# Sheet1_Young.net
KiCad netlist of a schematic drawn in Altium Designer
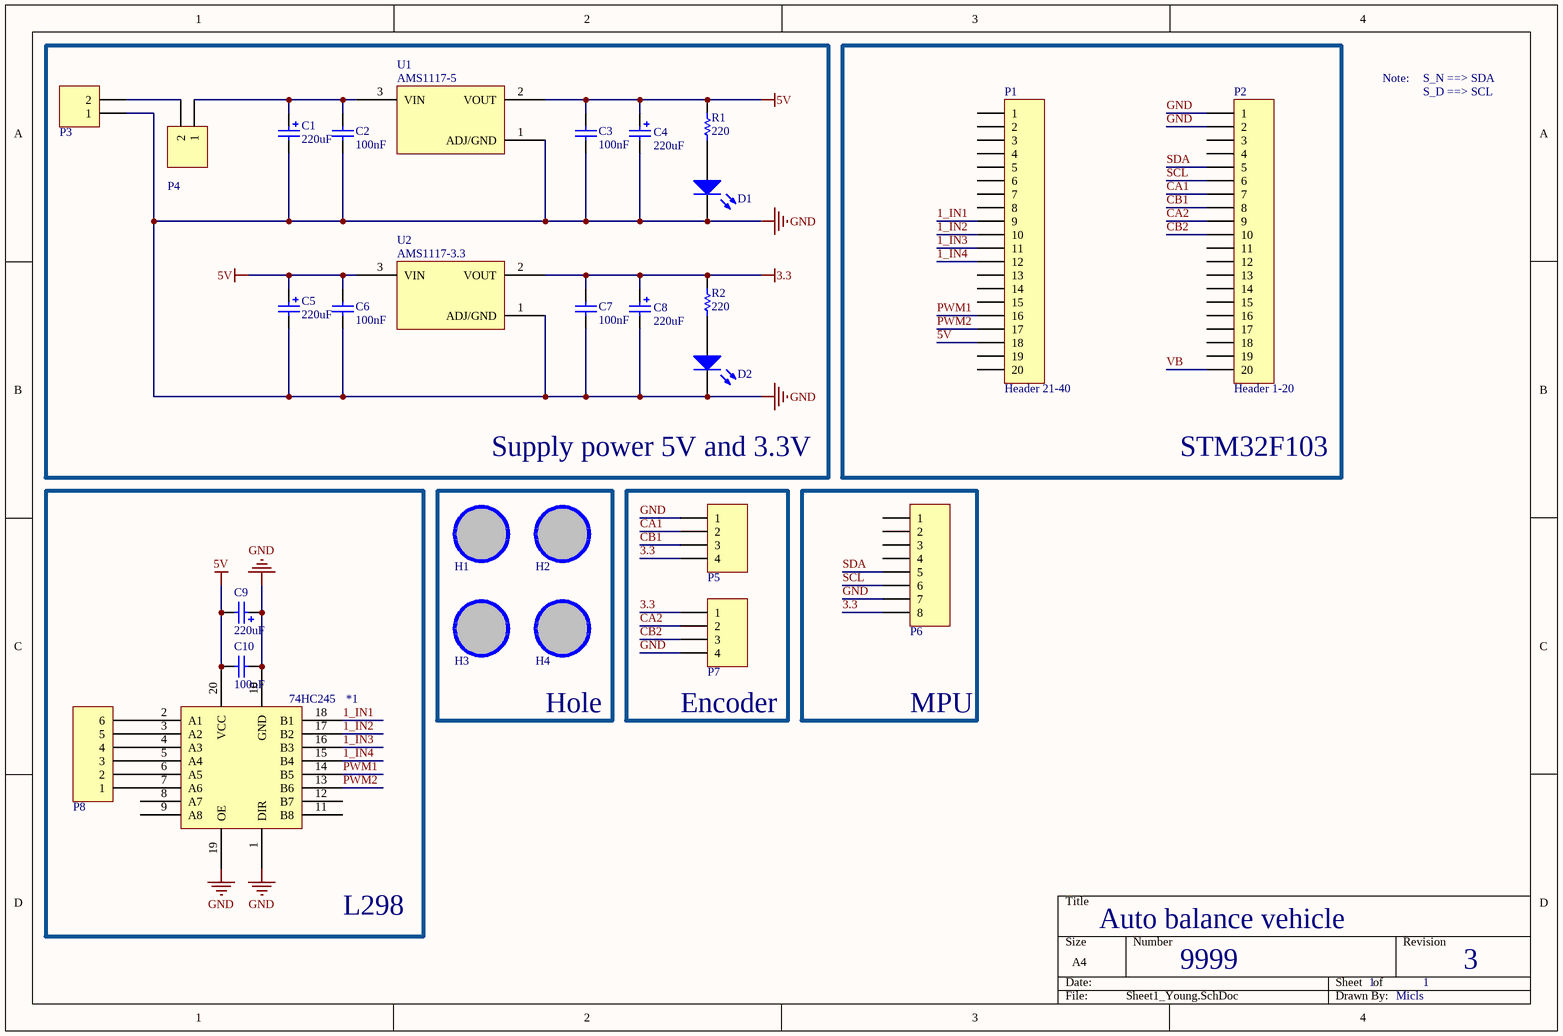
[diagram p0: Sheet1_Young.SchDoc]

(export (version "E")
  (design (tool "Eeschema 10.0.6"))
  (components
    (comp (ref "*1")
      (value "74HC245")
      (footprint "DIP20-3D")
      (libsource (lib "Bus Transceiver") (part "74HC245"))
    )
    (comp (ref "C1")
      (value "220uF")
      (footprint "CAP ALU SIZE B")
      (description "Polarized Capacitor (Radial)")
      (fields (field (name "Comment") "Cap Pol SMD"))
      (libsource (lib "PIF_Library") (part "Cap Pol SMD"))
    )
    (comp (ref "C2")
      (value "100nF")
      (footprint "CAP-SM-0805")
      (description "Capacitor")
      (fields (field (name "Comment") "Cap Non-Pol SMD"))
      (libsource (lib "PIF_Library") (part "Cap Non-Pol SMD"))
    )
    (comp (ref "C3")
      (value "100nF")
      (footprint "CAP-SM-0805")
      (description "Capacitor")
      (fields (field (name "Comment") "Cap Non-Pol SMD"))
      (libsource (lib "PIF_Library") (part "Cap Non-Pol SMD"))
    )
    (comp (ref "C4")
      (value "220uF")
      (footprint "CAP ALU SIZE B")
      (description "Polarized Capacitor (Radial)")
      (fields (field (name "Comment") "Cap Pol SMD"))
      (libsource (lib "PIF_Library") (part "Cap Pol SMD"))
    )
    (comp (ref "C5")
      (value "220uF")
      (footprint "CAP ALU SIZE B")
      (description "Polarized Capacitor (Radial)")
      (fields (field (name "Comment") "Cap Pol SMD"))
      (libsource (lib "PIF_Library") (part "Cap Pol SMD"))
    )
    (comp (ref "C6")
      (value "100nF")
      (footprint "CAP-SM-0805")
      (description "Capacitor")
      (fields (field (name "Comment") "Cap Non-Pol SMD"))
      (libsource (lib "PIF_Library") (part "Cap Non-Pol SMD"))
    )
    (comp (ref "C7")
      (value "100nF")
      (footprint "CAP-SM-0805")
      (description "Capacitor")
      (fields (field (name "Comment") "Cap Non-Pol SMD"))
      (libsource (lib "PIF_Library") (part "Cap Non-Pol SMD"))
    )
    (comp (ref "C8")
      (value "220uF")
      (footprint "CAP ALU SIZE B")
      (description "Polarized Capacitor (Radial)")
      (fields (field (name "Comment") "Cap Pol SMD"))
      (libsource (lib "PIF_Library") (part "Cap Pol SMD"))
    )
    (comp (ref "C9")
      (value "220uF")
      (footprint "CAP ALU SIZE B")
      (description "Polarized Capacitor (Radial)")
      (fields (field (name "Comment") "Cap Pol SMD"))
      (libsource (lib "PIF_Library") (part "Cap Pol SMD"))
    )
    (comp (ref "C10")
      (value "100nF")
      (footprint "CAP-SM-0805")
      (description "Capacitor")
      (fields (field (name "Comment") "Cap Non-Pol SMD"))
      (libsource (lib "PIF_Library") (part "Cap Non-Pol SMD"))
    )
    (comp (ref "D1")
      (value "LED SMD")
      (footprint "LED_0805_Blue")
      (description "LED")
      (libsource (lib "PIF_Library") (part "LED SMD"))
    )
    (comp (ref "D2")
      (value "LED SMD")
      (footprint "LED_0805_Blue")
      (description "LED")
      (libsource (lib "PIF_Library") (part "LED SMD"))
    )
    (comp (ref "H1")
      (value "Hole")
      (footprint "LO KHOAN 3MM")
      (description "Hole 3mm")
      (libsource (lib "PIF_Library") (part "Hole"))
    )
    (comp (ref "H2")
      (value "Hole")
      (footprint "LO KHOAN 3MM")
      (description "Hole 3mm")
      (libsource (lib "PIF_Library") (part "Hole"))
    )
    (comp (ref "H3")
      (value "Hole")
      (footprint "LO KHOAN 3MM")
      (description "Hole 3mm")
      (libsource (lib "PIF_Library") (part "Hole"))
    )
    (comp (ref "H4")
      (value "Hole")
      (footprint "LO KHOAN 3MM")
      (description "Hole 3mm")
      (libsource (lib "PIF_Library") (part "Hole"))
    )
    (comp (ref "P1")
      (value "Header 21-40")
      (footprint "HDR1X20")
      (description "Header, 20-Pin")
      (fields (field (name "PUBLISHER") "Altium Limited"))
      (libsource (lib "Miscellaneous Connectors") (part "Header 20"))
    )
    (comp (ref "P2")
      (value "Header 1-20")
      (footprint "HDR1X20")
      (description "Header, 20-Pin")
      (fields (field (name "PUBLISHER") "Altium Limited"))
      (libsource (lib "Miscellaneous Connectors") (part "Header 20"))
    )
    (comp (ref "P3")
      (value "Domino 2")
      (footprint "DOMINO 2- 5mm")
      (description "Domino, 2-Pin")
      (fields (field (name "PUBLISHER") "Altium Limited"))
      (libsource (lib "PIF_Library") (part "Domino 2"))
    )
    (comp (ref "P4")
      (value "Domino 2")
      (footprint "DOMINO 2- 5mm")
      (description "Domino, 2-Pin")
      (fields (field (name "PUBLISHER") "Altium Limited"))
      (libsource (lib "") (part "Domino 2_1"))
    )
    (comp (ref "P5")
      (value "Header 4")
      (footprint "JP4")
      (description "Header, 4-Pin")
      (fields (field (name "PUBLISHER") "Altium Limited"))
      (libsource (lib "PIF_Library") (part "Header 4"))
    )
    (comp (ref "P6")
      (value "Header 8")
      (footprint "JP8")
      (description "Header, 8-Pin")
      (fields (field (name "PUBLISHER") "Altium Limited"))
      (libsource (lib "PIF_Library") (part "Header 8"))
    )
    (comp (ref "P7")
      (value "Header 4")
      (footprint "JP4")
      (description "Header, 4-Pin")
      (fields (field (name "PUBLISHER") "Altium Limited"))
      (libsource (lib "PIF_Library") (part "Header 4"))
    )
    (comp (ref "P8")
      (value "Header 6")
      (footprint "JP6")
      (description "Header, 6-Pin")
      (fields (field (name "PUBLISHER") "Altium Limited"))
      (libsource (lib "PIF_Library") (part "Header 6"))
    )
    (comp (ref "R1")
      (value "220")
      (footprint "RES-SM-0805")
      (description "Resistor")
      (fields (field (name "Comment") "RESISTOR SMD"))
      (libsource (lib "PIF_Library") (part "RESISTOR SMD"))
    )
    (comp (ref "R2")
      (value "220")
      (footprint "RES-SM-0805")
      (description "Resistor")
      (fields (field (name "Comment") "RESISTOR SMD"))
      (libsource (lib "PIF_Library") (part "RESISTOR SMD"))
    )
    (comp (ref "U1")
      (value "AMS1117-5")
      (footprint "SOT230P700X180-4N")
      (fields (field (name "MP") "AMS1117-3.3") (field (name "MF") "NEC"))
      (libsource (lib "AMS1117-3.3") (part "AMS1117-3.3"))
    )
    (comp (ref "U2")
      (value "AMS1117-3.3")
      (footprint "SOT230P700X180-4N")
      (fields (field (name "MF") "NEC"))
      (libsource (lib "AMS1117-3.3") (part "AMS1117-3.3"))
    )
  )
  (nets
    (net (code "1") (name "/1_IN1") (class "Default")
      (node (ref "*1") (pin "18") (pinfunction "B1_18") (pintype "passive"))
      (node (ref "P1") (pin "9") (pinfunction "9_9") (pintype "passive"))
    )
    (net (code "2") (name "/1_IN2") (class "Default")
      (node (ref "*1") (pin "17") (pinfunction "B2_17") (pintype "passive"))
      (node (ref "P1") (pin "10") (pinfunction "10_10") (pintype "passive"))
    )
    (net (code "3") (name "/1_IN3") (class "Default")
      (node (ref "*1") (pin "16") (pinfunction "B3_16") (pintype "passive"))
      (node (ref "P1") (pin "11") (pinfunction "11_11") (pintype "passive"))
    )
    (net (code "4") (name "/1_IN4") (class "Default")
      (node (ref "*1") (pin "15") (pinfunction "B4_15") (pintype "passive"))
      (node (ref "P1") (pin "12") (pinfunction "12_12") (pintype "passive"))
    )
    (net (code "5") (name "/CA1") (class "Default")
      (node (ref "P2") (pin "7") (pinfunction "7_7") (pintype "passive"))
      (node (ref "P5") (pin "2") (pinfunction "2_2") (pintype "passive"))
    )
    (net (code "6") (name "/CA2") (class "Default")
      (node (ref "P2") (pin "9") (pinfunction "9_9") (pintype "passive"))
      (node (ref "P7") (pin "2") (pinfunction "2_2") (pintype "passive"))
    )
    (net (code "7") (name "/CB1") (class "Default")
      (node (ref "P2") (pin "8") (pinfunction "8_8") (pintype "passive"))
      (node (ref "P5") (pin "3") (pinfunction "3_3") (pintype "passive"))
    )
    (net (code "8") (name "/CB2") (class "Default")
      (node (ref "P2") (pin "10") (pinfunction "10_10") (pintype "passive"))
      (node (ref "P7") (pin "3") (pinfunction "3_3") (pintype "passive"))
    )
    (net (code "9") (name "/PWM1") (class "Default")
      (node (ref "*1") (pin "14") (pinfunction "B5_14") (pintype "passive"))
      (node (ref "P1") (pin "16") (pinfunction "16_16") (pintype "passive"))
    )
    (net (code "10") (name "/PWM2") (class "Default")
      (node (ref "*1") (pin "13") (pinfunction "B6_13") (pintype "passive"))
      (node (ref "P1") (pin "17") (pinfunction "17_17") (pintype "passive"))
    )
    (net (code "11") (name "/SCL") (class "Default")
      (node (ref "P2") (pin "6") (pinfunction "6_6") (pintype "passive"))
      (node (ref "P6") (pin "6") (pinfunction "6_6") (pintype "passive"))
    )
    (net (code "12") (name "/SDA") (class "Default")
      (node (ref "P2") (pin "5") (pinfunction "5_5") (pintype "passive"))
      (node (ref "P6") (pin "5") (pinfunction "5_5") (pintype "passive"))
    )
    (net (code "13") (name "/VB") (class "Default")
      (node (ref "P2") (pin "20") (pinfunction "20_20") (pintype "passive"))
    )
    (net (code "14") (name "3.3") (class "Default")
      (node (ref "C7") (pin "1") (pinfunction "1_1") (pintype "passive"))
      (node (ref "C8") (pin "1") (pinfunction "1_1") (pintype "passive"))
      (node (ref "P5") (pin "4") (pinfunction "4_4") (pintype "passive"))
      (node (ref "P6") (pin "8") (pinfunction "8_8") (pintype "passive"))
      (node (ref "P7") (pin "1") (pinfunction "1_1") (pintype "passive"))
      (node (ref "R2") (pin "2") (pinfunction "2_2") (pintype "passive"))
      (node (ref "U2") (pin "2") (pinfunction "VOUT_2") (pintype "passive"))
    )
    (net (code "15") (name "5V") (class "Default")
      (node (ref "*1") (pin "20") (pinfunction "VCC_20") (pintype "passive"))
      (node (ref "C10") (pin "1") (pinfunction "1_1") (pintype "passive"))
      (node (ref "C3") (pin "1") (pinfunction "1_1") (pintype "passive"))
      (node (ref "C4") (pin "1") (pinfunction "1_1") (pintype "passive"))
      (node (ref "C5") (pin "1") (pinfunction "1_1") (pintype "passive"))
      (node (ref "C6") (pin "2") (pinfunction "2_2") (pintype "passive"))
      (node (ref "C9") (pin "2") (pinfunction "2_2") (pintype "passive"))
      (node (ref "P1") (pin "18") (pinfunction "18_18") (pintype "passive"))
      (node (ref "R1") (pin "2") (pinfunction "2_2") (pintype "passive"))
      (node (ref "U1") (pin "2") (pinfunction "VOUT_2") (pintype "passive"))
      (node (ref "U2") (pin "3") (pinfunction "VIN_3") (pintype "passive"))
    )
    (net (code "16") (name "GND") (class "Default")
      (node (ref "*1") (pin "1") (pinfunction "DIR_1") (pintype "passive"))
      (node (ref "*1") (pin "10") (pinfunction "GND_10") (pintype "passive"))
      (node (ref "*1") (pin "19") (pinfunction "OE_19") (pintype "passive"))
      (node (ref "C1") (pin "2") (pinfunction "2_2") (pintype "passive"))
      (node (ref "C10") (pin "2") (pinfunction "2_2") (pintype "passive"))
      (node (ref "C2") (pin "1") (pinfunction "1_1") (pintype "passive"))
      (node (ref "C3") (pin "2") (pinfunction "2_2") (pintype "passive"))
      (node (ref "C4") (pin "2") (pinfunction "2_2") (pintype "passive"))
      (node (ref "C5") (pin "2") (pinfunction "2_2") (pintype "passive"))
      (node (ref "C6") (pin "1") (pinfunction "1_1") (pintype "passive"))
      (node (ref "C7") (pin "2") (pinfunction "2_2") (pintype "passive"))
      (node (ref "C8") (pin "2") (pinfunction "2_2") (pintype "passive"))
      (node (ref "C9") (pin "1") (pinfunction "1_1") (pintype "passive"))
      (node (ref "D1") (pin "2") (pinfunction "K_2") (pintype "passive"))
      (node (ref "D2") (pin "2") (pinfunction "K_2") (pintype "passive"))
      (node (ref "P2") (pin "1") (pinfunction "1_1") (pintype "passive"))
      (node (ref "P2") (pin "2") (pinfunction "2_2") (pintype "passive"))
      (node (ref "P3") (pin "1") (pinfunction "1_1") (pintype "passive"))
      (node (ref "P5") (pin "1") (pinfunction "1_1") (pintype "passive"))
      (node (ref "P6") (pin "7") (pinfunction "7_7") (pintype "passive"))
      (node (ref "P7") (pin "4") (pinfunction "4_4") (pintype "passive"))
      (node (ref "U1") (pin "1") (pinfunction "ADJ/GND_1") (pintype "passive"))
      (node (ref "U2") (pin "1") (pinfunction "ADJ/GND_1") (pintype "passive"))
    )
    (net (code "17") (name "Net-(*1-A1)") (class "Default")
      (node (ref "*1") (pin "2") (pinfunction "A1_2") (pintype "passive"))
      (node (ref "P8") (pin "6") (pinfunction "6_6") (pintype "passive"))
    )
    (net (code "18") (name "Net-(*1-A2)") (class "Default")
      (node (ref "*1") (pin "3") (pinfunction "A2_3") (pintype "passive"))
      (node (ref "P8") (pin "5") (pinfunction "5_5") (pintype "passive"))
    )
    (net (code "19") (name "Net-(*1-A3)") (class "Default")
      (node (ref "*1") (pin "4") (pinfunction "A3_4") (pintype "passive"))
      (node (ref "P8") (pin "4") (pinfunction "4_4") (pintype "passive"))
    )
    (net (code "20") (name "Net-(*1-A4)") (class "Default")
      (node (ref "*1") (pin "5") (pinfunction "A4_5") (pintype "passive"))
      (node (ref "P8") (pin "3") (pinfunction "3_3") (pintype "passive"))
    )
    (net (code "21") (name "Net-(*1-A5)") (class "Default")
      (node (ref "*1") (pin "6") (pinfunction "A5_6") (pintype "passive"))
      (node (ref "P8") (pin "2") (pinfunction "2_2") (pintype "passive"))
    )
    (net (code "22") (name "Net-(*1-A6)") (class "Default")
      (node (ref "*1") (pin "7") (pinfunction "A6_7") (pintype "passive"))
      (node (ref "P8") (pin "1") (pinfunction "1_1") (pintype "passive"))
    )
    (net (code "23") (name "Net-(D1-A)") (class "Default")
      (node (ref "D1") (pin "1") (pinfunction "A_1") (pintype "passive"))
      (node (ref "R1") (pin "1") (pinfunction "1_1") (pintype "passive"))
    )
    (net (code "24") (name "Net-(D2-A)") (class "Default")
      (node (ref "D2") (pin "1") (pinfunction "A_1") (pintype "passive"))
      (node (ref "R2") (pin "1") (pinfunction "1_1") (pintype "passive"))
    )
    (net (code "25") (name "Net-(P3-Pad2)") (class "Default")
      (node (ref "P3") (pin "2") (pinfunction "2_2") (pintype "passive"))
      (node (ref "P4") (pin "2") (pinfunction "2_2") (pintype "passive"))
    )
    (net (code "26") (name "Net-(U1-VIN)") (class "Default")
      (node (ref "C1") (pin "1") (pinfunction "1_1") (pintype "passive"))
      (node (ref "C2") (pin "2") (pinfunction "2_2") (pintype "passive"))
      (node (ref "P4") (pin "1") (pinfunction "1_1") (pintype "passive"))
      (node (ref "U1") (pin "3") (pinfunction "VIN_3") (pintype "passive"))
    )
    (net (code "27") (name "unconnected-(*1-A7-Pad8)") (class "Default")
      (node (ref "*1") (pin "8") (pinfunction "A7_8") (pintype "passive"))
    )
    (net (code "28") (name "unconnected-(*1-A8-Pad9)") (class "Default")
      (node (ref "*1") (pin "9") (pinfunction "A8_9") (pintype "passive"))
    )
    (net (code "29") (name "unconnected-(*1-B7-Pad12)") (class "Default")
      (node (ref "*1") (pin "12") (pinfunction "B7_12") (pintype "passive"))
    )
    (net (code "30") (name "unconnected-(*1-B8-Pad11)") (class "Default")
      (node (ref "*1") (pin "11") (pinfunction "B8_11") (pintype "passive"))
    )
    (net (code "31") (name "unconnected-(H1-Pad1)") (class "Default")
      (node (ref "H1") (pin "1") (pinfunction "1_1") (pintype "passive"))
    )
    (net (code "32") (name "unconnected-(H2-Pad1)") (class "Default")
      (node (ref "H2") (pin "1") (pinfunction "1_1") (pintype "passive"))
    )
    (net (code "33") (name "unconnected-(H3-Pad1)") (class "Default")
      (node (ref "H3") (pin "1") (pinfunction "1_1") (pintype "passive"))
    )
    (net (code "34") (name "unconnected-(H4-Pad1)") (class "Default")
      (node (ref "H4") (pin "1") (pinfunction "1_1") (pintype "passive"))
    )
    (net (code "35") (name "unconnected-(P1-Pad1)") (class "Default")
      (node (ref "P1") (pin "1") (pinfunction "1_1") (pintype "passive"))
    )
    (net (code "36") (name "unconnected-(P1-Pad2)") (class "Default")
      (node (ref "P1") (pin "2") (pinfunction "2_2") (pintype "passive"))
    )
    (net (code "37") (name "unconnected-(P1-Pad3)") (class "Default")
      (node (ref "P1") (pin "3") (pinfunction "3_3") (pintype "passive"))
    )
    (net (code "38") (name "unconnected-(P1-Pad4)") (class "Default")
      (node (ref "P1") (pin "4") (pinfunction "4_4") (pintype "passive"))
    )
    (net (code "39") (name "unconnected-(P1-Pad5)") (class "Default")
      (node (ref "P1") (pin "5") (pinfunction "5_5") (pintype "passive"))
    )
    (net (code "40") (name "unconnected-(P1-Pad6)") (class "Default")
      (node (ref "P1") (pin "6") (pinfunction "6_6") (pintype "passive"))
    )
    (net (code "41") (name "unconnected-(P1-Pad7)") (class "Default")
      (node (ref "P1") (pin "7") (pinfunction "7_7") (pintype "passive"))
    )
    (net (code "42") (name "unconnected-(P1-Pad8)") (class "Default")
      (node (ref "P1") (pin "8") (pinfunction "8_8") (pintype "passive"))
    )
    (net (code "43") (name "unconnected-(P1-Pad13)") (class "Default")
      (node (ref "P1") (pin "13") (pinfunction "13_13") (pintype "passive"))
    )
    (net (code "44") (name "unconnected-(P1-Pad14)") (class "Default")
      (node (ref "P1") (pin "14") (pinfunction "14_14") (pintype "passive"))
    )
    (net (code "45") (name "unconnected-(P1-Pad15)") (class "Default")
      (node (ref "P1") (pin "15") (pinfunction "15_15") (pintype "passive"))
    )
    (net (code "46") (name "unconnected-(P1-Pad19)") (class "Default")
      (node (ref "P1") (pin "19") (pinfunction "19_19") (pintype "passive"))
    )
    (net (code "47") (name "unconnected-(P1-Pad20)") (class "Default")
      (node (ref "P1") (pin "20") (pinfunction "20_20") (pintype "passive"))
    )
    (net (code "48") (name "unconnected-(P2-Pad3)") (class "Default")
      (node (ref "P2") (pin "3") (pinfunction "3_3") (pintype "passive"))
    )
    (net (code "49") (name "unconnected-(P2-Pad4)") (class "Default")
      (node (ref "P2") (pin "4") (pinfunction "4_4") (pintype "passive"))
    )
    (net (code "50") (name "unconnected-(P2-Pad11)") (class "Default")
      (node (ref "P2") (pin "11") (pinfunction "11_11") (pintype "passive"))
    )
    (net (code "51") (name "unconnected-(P2-Pad12)") (class "Default")
      (node (ref "P2") (pin "12") (pinfunction "12_12") (pintype "passive"))
    )
    (net (code "52") (name "unconnected-(P2-Pad13)") (class "Default")
      (node (ref "P2") (pin "13") (pinfunction "13_13") (pintype "passive"))
    )
    (net (code "53") (name "unconnected-(P2-Pad14)") (class "Default")
      (node (ref "P2") (pin "14") (pinfunction "14_14") (pintype "passive"))
    )
    (net (code "54") (name "unconnected-(P2-Pad15)") (class "Default")
      (node (ref "P2") (pin "15") (pinfunction "15_15") (pintype "passive"))
    )
    (net (code "55") (name "unconnected-(P2-Pad16)") (class "Default")
      (node (ref "P2") (pin "16") (pinfunction "16_16") (pintype "passive"))
    )
    (net (code "56") (name "unconnected-(P2-Pad17)") (class "Default")
      (node (ref "P2") (pin "17") (pinfunction "17_17") (pintype "passive"))
    )
    (net (code "57") (name "unconnected-(P2-Pad18)") (class "Default")
      (node (ref "P2") (pin "18") (pinfunction "18_18") (pintype "passive"))
    )
    (net (code "58") (name "unconnected-(P2-Pad19)") (class "Default")
      (node (ref "P2") (pin "19") (pinfunction "19_19") (pintype "passive"))
    )
    (net (code "59") (name "unconnected-(P6-Pad1)") (class "Default")
      (node (ref "P6") (pin "1") (pinfunction "1_1") (pintype "passive"))
    )
    (net (code "60") (name "unconnected-(P6-Pad2)") (class "Default")
      (node (ref "P6") (pin "2") (pinfunction "2_2") (pintype "passive"))
    )
    (net (code "61") (name "unconnected-(P6-Pad3)") (class "Default")
      (node (ref "P6") (pin "3") (pinfunction "3_3") (pintype "passive"))
    )
    (net (code "62") (name "unconnected-(P6-Pad4)") (class "Default")
      (node (ref "P6") (pin "4") (pinfunction "4_4") (pintype "passive"))
    )
  )
)
